# Schemtaic.net
KiCad netlist of a schematic drawn in Altium Designer
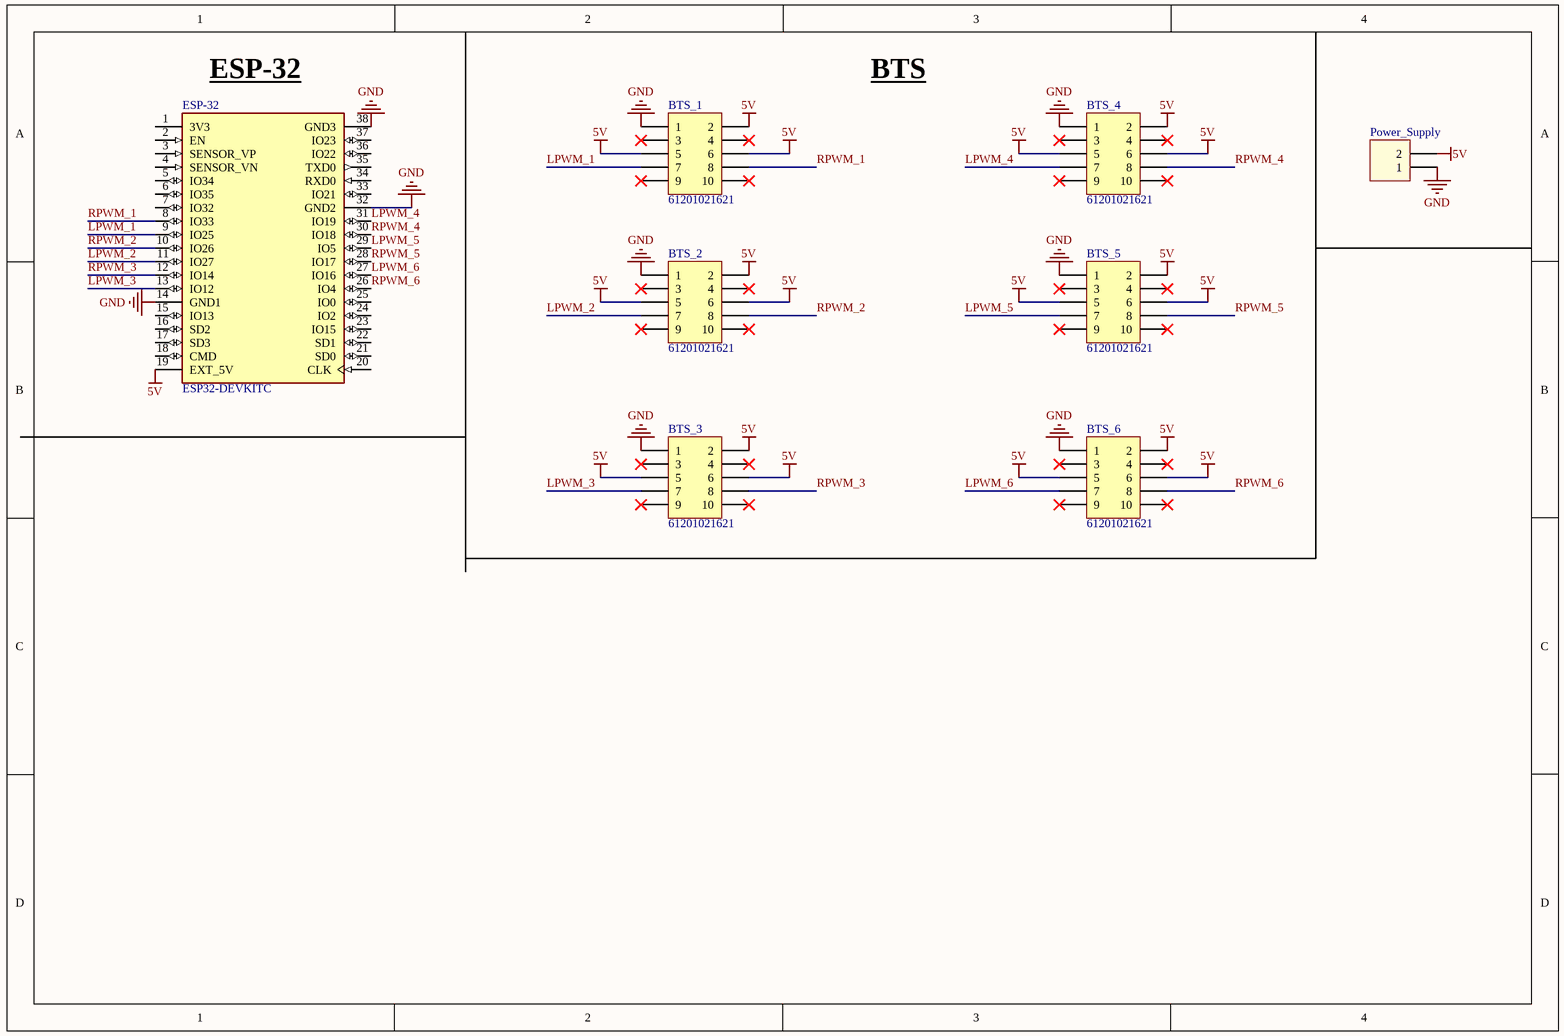
[diagram p0: Schemtaic.SchDoc]

(export (version "E")
  (design (tool "Eeschema 10.0.6"))
  (components
    (comp (ref "BTS_1")
      (value "61201021621")
      (footprint "61201021621")
      (description "WR-BHD 2.54mm Male Box Header")
      (fields (field (name "MANUFACTURER") "Wurth Elektronik") (field (name "CREATED BY") "Baojun Chen"))
      (libsource (lib "FRC Base") (part "61201021621"))
    )
    (comp (ref "BTS_2")
      (value "61201021621")
      (footprint "61201021621")
      (description "WR-BHD 2.54mm Male Box Header")
      (fields (field (name "MANUFACTURER") "Wurth Elektronik") (field (name "CREATED BY") "Baojun Chen"))
      (libsource (lib "FRC Base") (part "61201021621"))
    )
    (comp (ref "BTS_3")
      (value "61201021621")
      (footprint "61201021621")
      (description "WR-BHD 2.54mm Male Box Header")
      (fields (field (name "MANUFACTURER") "Wurth Elektronik") (field (name "CREATED BY") "Baojun Chen"))
      (libsource (lib "FRC Base") (part "61201021621"))
    )
    (comp (ref "BTS_4")
      (value "61201021621")
      (footprint "61201021621")
      (description "WR-BHD 2.54mm Male Box Header")
      (fields (field (name "MANUFACTURER") "Wurth Elektronik") (field (name "CREATED BY") "Baojun Chen"))
      (libsource (lib "FRC Base") (part "61201021621"))
    )
    (comp (ref "BTS_5")
      (value "61201021621")
      (footprint "61201021621")
      (description "WR-BHD 2.54mm Male Box Header")
      (fields (field (name "MANUFACTURER") "Wurth Elektronik") (field (name "CREATED BY") "Baojun Chen"))
      (libsource (lib "FRC Base") (part "61201021621"))
    )
    (comp (ref "BTS_6")
      (value "61201021621")
      (footprint "61201021621")
      (description "WR-BHD 2.54mm Male Box Header")
      (fields (field (name "MANUFACTURER") "Wurth Elektronik") (field (name "CREATED BY") "Baojun Chen"))
      (libsource (lib "FRC Base") (part "61201021621"))
    )
    (comp (ref "ESP-32")
      (value "ESP32-DEVKITC")
      (footprint "MODULE_ESP32-DEVKITC")
      (fields (field (name "MF") "Espressif Systems"))
      (libsource (lib "ESP32-DEVKITC") (part "ESP32-DEVKITC"))
    )
    (comp (ref "Power_Supply")
      (value "691311700102")
      (footprint "691311700102")
      (description "WR-TBL Serie 3117 - 5.00 mm Close Vertical PCB Header, 02p")
      (fields (field (name "PUBLISHER") "Wurth Elektronik"))
      (libsource (lib "Phoenix - Female 5mm") (part "691311700102"))
    )
  )
  (nets
    (net (code "1") (name "/LPWM_1") (class "Default")
      (node (ref "BTS_1") (pin "7") (pinfunction "7_7") (pintype "passive"))
      (node (ref "ESP-32") (pin "9") (pinfunction "IO25_9") (pintype "bidirectional"))
    )
    (net (code "2") (name "/LPWM_2") (class "Default")
      (node (ref "BTS_2") (pin "7") (pinfunction "7_7") (pintype "passive"))
      (node (ref "ESP-32") (pin "11") (pinfunction "IO27_11") (pintype "bidirectional"))
    )
    (net (code "3") (name "/LPWM_3") (class "Default")
      (node (ref "BTS_3") (pin "7") (pinfunction "7_7") (pintype "passive"))
      (node (ref "ESP-32") (pin "13") (pinfunction "IO12_13") (pintype "bidirectional"))
    )
    (net (code "4") (name "/LPWM_4") (class "Default")
      (node (ref "BTS_4") (pin "7") (pinfunction "7_7") (pintype "passive"))
      (node (ref "ESP-32") (pin "31") (pinfunction "IO19_31") (pintype "bidirectional"))
    )
    (net (code "5") (name "/LPWM_5") (class "Default")
      (node (ref "BTS_5") (pin "7") (pinfunction "7_7") (pintype "passive"))
      (node (ref "ESP-32") (pin "29") (pinfunction "IO5_29") (pintype "bidirectional"))
    )
    (net (code "6") (name "/LPWM_6") (class "Default")
      (node (ref "BTS_6") (pin "7") (pinfunction "7_7") (pintype "passive"))
      (node (ref "ESP-32") (pin "27") (pinfunction "IO16_27") (pintype "bidirectional"))
    )
    (net (code "7") (name "/RPWM_1") (class "Default")
      (node (ref "BTS_1") (pin "8") (pinfunction "8_8") (pintype "passive"))
      (node (ref "ESP-32") (pin "8") (pinfunction "IO33_8") (pintype "bidirectional"))
    )
    (net (code "8") (name "/RPWM_2") (class "Default")
      (node (ref "BTS_2") (pin "8") (pinfunction "8_8") (pintype "passive"))
      (node (ref "ESP-32") (pin "10") (pinfunction "IO26_10") (pintype "bidirectional"))
    )
    (net (code "9") (name "/RPWM_3") (class "Default")
      (node (ref "BTS_3") (pin "8") (pinfunction "8_8") (pintype "passive"))
      (node (ref "ESP-32") (pin "12") (pinfunction "IO14_12") (pintype "bidirectional"))
    )
    (net (code "10") (name "/RPWM_4") (class "Default")
      (node (ref "BTS_4") (pin "8") (pinfunction "8_8") (pintype "passive"))
      (node (ref "ESP-32") (pin "30") (pinfunction "IO18_30") (pintype "bidirectional"))
    )
    (net (code "11") (name "/RPWM_5") (class "Default")
      (node (ref "BTS_5") (pin "8") (pinfunction "8_8") (pintype "passive"))
      (node (ref "ESP-32") (pin "28") (pinfunction "IO17_28") (pintype "bidirectional"))
    )
    (net (code "12") (name "/RPWM_6") (class "Default")
      (node (ref "BTS_6") (pin "8") (pinfunction "8_8") (pintype "passive"))
      (node (ref "ESP-32") (pin "26") (pinfunction "IO4_26") (pintype "bidirectional"))
    )
    (net (code "13") (name "5V") (class "Default")
      (node (ref "BTS_1") (pin "2") (pinfunction "2_2") (pintype "passive"))
      (node (ref "BTS_1") (pin "5") (pinfunction "5_5") (pintype "passive"))
      (node (ref "BTS_1") (pin "6") (pinfunction "6_6") (pintype "passive"))
      (node (ref "BTS_2") (pin "2") (pinfunction "2_2") (pintype "passive"))
      (node (ref "BTS_2") (pin "5") (pinfunction "5_5") (pintype "passive"))
      (node (ref "BTS_2") (pin "6") (pinfunction "6_6") (pintype "passive"))
      (node (ref "BTS_3") (pin "2") (pinfunction "2_2") (pintype "passive"))
      (node (ref "BTS_3") (pin "5") (pinfunction "5_5") (pintype "passive"))
      (node (ref "BTS_3") (pin "6") (pinfunction "6_6") (pintype "passive"))
      (node (ref "BTS_4") (pin "2") (pinfunction "2_2") (pintype "passive"))
      (node (ref "BTS_4") (pin "5") (pinfunction "5_5") (pintype "passive"))
      (node (ref "BTS_4") (pin "6") (pinfunction "6_6") (pintype "passive"))
      (node (ref "BTS_5") (pin "2") (pinfunction "2_2") (pintype "passive"))
      (node (ref "BTS_5") (pin "5") (pinfunction "5_5") (pintype "passive"))
      (node (ref "BTS_5") (pin "6") (pinfunction "6_6") (pintype "passive"))
      (node (ref "BTS_6") (pin "2") (pinfunction "2_2") (pintype "passive"))
      (node (ref "BTS_6") (pin "5") (pinfunction "5_5") (pintype "passive"))
      (node (ref "BTS_6") (pin "6") (pinfunction "6_6") (pintype "passive"))
      (node (ref "ESP-32") (pin "19") (pinfunction "EXT_5V_19") (pintype "power_in"))
      (node (ref "Power_Supply") (pin "2") (pinfunction "2_2") (pintype "passive"))
    )
    (net (code "14") (name "GND") (class "Default")
      (node (ref "BTS_1") (pin "1") (pinfunction "1_1") (pintype "passive"))
      (node (ref "BTS_2") (pin "1") (pinfunction "1_1") (pintype "passive"))
      (node (ref "BTS_3") (pin "1") (pinfunction "1_1") (pintype "passive"))
      (node (ref "BTS_4") (pin "1") (pinfunction "1_1") (pintype "passive"))
      (node (ref "BTS_5") (pin "1") (pinfunction "1_1") (pintype "passive"))
      (node (ref "BTS_6") (pin "1") (pinfunction "1_1") (pintype "passive"))
      (node (ref "ESP-32") (pin "14") (pinfunction "GND1_14") (pintype "power_in"))
      (node (ref "ESP-32") (pin "32") (pinfunction "GND2_32") (pintype "power_in"))
      (node (ref "ESP-32") (pin "38") (pinfunction "GND3_38") (pintype "power_in"))
      (node (ref "Power_Supply") (pin "1") (pinfunction "1_1") (pintype "passive"))
    )
    (net (code "15") (name "unconnected-(BTS_1-Pad3)") (class "Default")
      (node (ref "BTS_1") (pin "3") (pinfunction "3_3") (pintype "passive+no_connect"))
    )
    (net (code "16") (name "unconnected-(BTS_1-Pad4)") (class "Default")
      (node (ref "BTS_1") (pin "4") (pinfunction "4_4") (pintype "passive+no_connect"))
    )
    (net (code "17") (name "unconnected-(BTS_1-Pad9)") (class "Default")
      (node (ref "BTS_1") (pin "9") (pinfunction "9_9") (pintype "passive+no_connect"))
    )
    (net (code "18") (name "unconnected-(BTS_1-Pad10)") (class "Default")
      (node (ref "BTS_1") (pin "10") (pinfunction "10_10") (pintype "passive+no_connect"))
    )
    (net (code "19") (name "unconnected-(BTS_2-Pad3)") (class "Default")
      (node (ref "BTS_2") (pin "3") (pinfunction "3_3") (pintype "passive+no_connect"))
    )
    (net (code "20") (name "unconnected-(BTS_2-Pad4)") (class "Default")
      (node (ref "BTS_2") (pin "4") (pinfunction "4_4") (pintype "passive+no_connect"))
    )
    (net (code "21") (name "unconnected-(BTS_2-Pad9)") (class "Default")
      (node (ref "BTS_2") (pin "9") (pinfunction "9_9") (pintype "passive+no_connect"))
    )
    (net (code "22") (name "unconnected-(BTS_2-Pad10)") (class "Default")
      (node (ref "BTS_2") (pin "10") (pinfunction "10_10") (pintype "passive+no_connect"))
    )
    (net (code "23") (name "unconnected-(BTS_3-Pad3)") (class "Default")
      (node (ref "BTS_3") (pin "3") (pinfunction "3_3") (pintype "passive+no_connect"))
    )
    (net (code "24") (name "unconnected-(BTS_3-Pad4)") (class "Default")
      (node (ref "BTS_3") (pin "4") (pinfunction "4_4") (pintype "passive+no_connect"))
    )
    (net (code "25") (name "unconnected-(BTS_3-Pad9)") (class "Default")
      (node (ref "BTS_3") (pin "9") (pinfunction "9_9") (pintype "passive+no_connect"))
    )
    (net (code "26") (name "unconnected-(BTS_3-Pad10)") (class "Default")
      (node (ref "BTS_3") (pin "10") (pinfunction "10_10") (pintype "passive+no_connect"))
    )
    (net (code "27") (name "unconnected-(BTS_4-Pad3)") (class "Default")
      (node (ref "BTS_4") (pin "3") (pinfunction "3_3") (pintype "passive+no_connect"))
    )
    (net (code "28") (name "unconnected-(BTS_4-Pad4)") (class "Default")
      (node (ref "BTS_4") (pin "4") (pinfunction "4_4") (pintype "passive+no_connect"))
    )
    (net (code "29") (name "unconnected-(BTS_4-Pad9)") (class "Default")
      (node (ref "BTS_4") (pin "9") (pinfunction "9_9") (pintype "passive+no_connect"))
    )
    (net (code "30") (name "unconnected-(BTS_4-Pad10)") (class "Default")
      (node (ref "BTS_4") (pin "10") (pinfunction "10_10") (pintype "passive+no_connect"))
    )
    (net (code "31") (name "unconnected-(BTS_5-Pad3)") (class "Default")
      (node (ref "BTS_5") (pin "3") (pinfunction "3_3") (pintype "passive+no_connect"))
    )
    (net (code "32") (name "unconnected-(BTS_5-Pad4)") (class "Default")
      (node (ref "BTS_5") (pin "4") (pinfunction "4_4") (pintype "passive+no_connect"))
    )
    (net (code "33") (name "unconnected-(BTS_5-Pad9)") (class "Default")
      (node (ref "BTS_5") (pin "9") (pinfunction "9_9") (pintype "passive+no_connect"))
    )
    (net (code "34") (name "unconnected-(BTS_5-Pad10)") (class "Default")
      (node (ref "BTS_5") (pin "10") (pinfunction "10_10") (pintype "passive+no_connect"))
    )
    (net (code "35") (name "unconnected-(BTS_6-Pad3)") (class "Default")
      (node (ref "BTS_6") (pin "3") (pinfunction "3_3") (pintype "passive+no_connect"))
    )
    (net (code "36") (name "unconnected-(BTS_6-Pad4)") (class "Default")
      (node (ref "BTS_6") (pin "4") (pinfunction "4_4") (pintype "passive+no_connect"))
    )
    (net (code "37") (name "unconnected-(BTS_6-Pad9)") (class "Default")
      (node (ref "BTS_6") (pin "9") (pinfunction "9_9") (pintype "passive+no_connect"))
    )
    (net (code "38") (name "unconnected-(BTS_6-Pad10)") (class "Default")
      (node (ref "BTS_6") (pin "10") (pinfunction "10_10") (pintype "passive+no_connect"))
    )
    (net (code "39") (name "unconnected-(ESP-32-3V3-Pad1)") (class "Default")
      (node (ref "ESP-32") (pin "1") (pinfunction "3V3_1") (pintype "power_in"))
    )
    (net (code "40") (name "unconnected-(ESP-32-CLK-Pad20)") (class "Default")
      (node (ref "ESP-32") (pin "20") (pinfunction "CLK_20") (pintype "input"))
    )
    (net (code "41") (name "unconnected-(ESP-32-CMD-Pad18)") (class "Default")
      (node (ref "ESP-32") (pin "18") (pinfunction "CMD_18") (pintype "bidirectional"))
    )
    (net (code "42") (name "unconnected-(ESP-32-EN-Pad2)") (class "Default")
      (node (ref "ESP-32") (pin "2") (pinfunction "EN_2") (pintype "input"))
    )
    (net (code "43") (name "unconnected-(ESP-32-IO0-Pad25)") (class "Default")
      (node (ref "ESP-32") (pin "25") (pinfunction "IO0_25") (pintype "bidirectional"))
    )
    (net (code "44") (name "unconnected-(ESP-32-IO2-Pad24)") (class "Default")
      (node (ref "ESP-32") (pin "24") (pinfunction "IO2_24") (pintype "bidirectional"))
    )
    (net (code "45") (name "unconnected-(ESP-32-IO13-Pad15)") (class "Default")
      (node (ref "ESP-32") (pin "15") (pinfunction "IO13_15") (pintype "bidirectional"))
    )
    (net (code "46") (name "unconnected-(ESP-32-IO15-Pad23)") (class "Default")
      (node (ref "ESP-32") (pin "23") (pinfunction "IO15_23") (pintype "bidirectional"))
    )
    (net (code "47") (name "unconnected-(ESP-32-IO21-Pad33)") (class "Default")
      (node (ref "ESP-32") (pin "33") (pinfunction "IO21_33") (pintype "bidirectional"))
    )
    (net (code "48") (name "unconnected-(ESP-32-IO22-Pad36)") (class "Default")
      (node (ref "ESP-32") (pin "36") (pinfunction "IO22_36") (pintype "bidirectional"))
    )
    (net (code "49") (name "unconnected-(ESP-32-IO23-Pad37)") (class "Default")
      (node (ref "ESP-32") (pin "37") (pinfunction "IO23_37") (pintype "bidirectional"))
    )
    (net (code "50") (name "unconnected-(ESP-32-IO32-Pad7)") (class "Default")
      (node (ref "ESP-32") (pin "7") (pinfunction "IO32_7") (pintype "bidirectional"))
    )
    (net (code "51") (name "unconnected-(ESP-32-IO34-Pad5)") (class "Default")
      (node (ref "ESP-32") (pin "5") (pinfunction "IO34_5") (pintype "bidirectional"))
    )
    (net (code "52") (name "unconnected-(ESP-32-IO35-Pad6)") (class "Default")
      (node (ref "ESP-32") (pin "6") (pinfunction "IO35_6") (pintype "bidirectional"))
    )
    (net (code "53") (name "unconnected-(ESP-32-RXD0-Pad34)") (class "Default")
      (node (ref "ESP-32") (pin "34") (pinfunction "RXD0_34") (pintype "input"))
    )
    (net (code "54") (name "unconnected-(ESP-32-SD0-Pad21)") (class "Default")
      (node (ref "ESP-32") (pin "21") (pinfunction "SD0_21") (pintype "bidirectional"))
    )
    (net (code "55") (name "unconnected-(ESP-32-SD1-Pad22)") (class "Default")
      (node (ref "ESP-32") (pin "22") (pinfunction "SD1_22") (pintype "bidirectional"))
    )
    (net (code "56") (name "unconnected-(ESP-32-SD2-Pad16)") (class "Default")
      (node (ref "ESP-32") (pin "16") (pinfunction "SD2_16") (pintype "bidirectional"))
    )
    (net (code "57") (name "unconnected-(ESP-32-SD3-Pad17)") (class "Default")
      (node (ref "ESP-32") (pin "17") (pinfunction "SD3_17") (pintype "bidirectional"))
    )
    (net (code "58") (name "unconnected-(ESP-32-SENSOR_VN-Pad4)") (class "Default")
      (node (ref "ESP-32") (pin "4") (pinfunction "SENSOR_VN_4") (pintype "input"))
    )
    (net (code "59") (name "unconnected-(ESP-32-SENSOR_VP-Pad3)") (class "Default")
      (node (ref "ESP-32") (pin "3") (pinfunction "SENSOR_VP_3") (pintype "input"))
    )
    (net (code "60") (name "unconnected-(ESP-32-TXD0-Pad35)") (class "Default")
      (node (ref "ESP-32") (pin "35") (pinfunction "TXD0_35") (pintype "output"))
    )
  )
)
